# Sensor_Board.net
KiCad netlist of a schematic drawn in Altium Designer
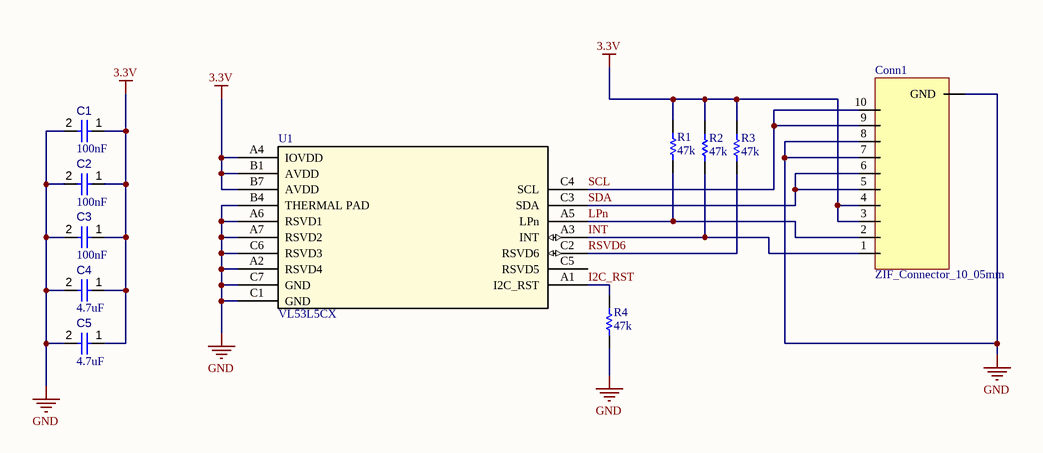
[diagram p0: Sensor_Board.SchDoc]

(export (version "E")
  (design (tool "Eeschema 10.0.6"))
  (components
    (comp (ref "C1")
      (value "100nF")
      (footprint "CAPC1608X90X40NL10T20")
      (description "Chip Capacitor, 100 nF, +/- 10%, 50 V, 0603 (1608 Metric)")
      (fields (field (name "TOLERANCE") "10%") (field (name "Comment") "Capacitor 100 nF +/-10% 50 V 0603"))
      (libsource (lib "Domen's Workpace") (part "CAP-NP-2"))
    )
    (comp (ref "C2")
      (value "100nF")
      (footprint "CAPC1608X90X40NL10T20")
      (description "Chip Capacitor, 100 nF, +/- 10%, 50 V, 0603 (1608 Metric)")
      (fields (field (name "TOLERANCE") "10%") (field (name "Comment") "Capacitor 100 nF +/-10% 50 V 0603"))
      (libsource (lib "Domen's Workpace") (part "CAP-NP-2"))
    )
    (comp (ref "C3")
      (value "100nF")
      (footprint "CAPC1608X90X40NL10T20")
      (description "Chip Capacitor, 100 nF, +/- 10%, 50 V, 0603 (1608 Metric)")
      (fields (field (name "TOLERANCE") "10%") (field (name "Comment") "Capacitor 100 nF +/-10% 50 V 0603"))
      (libsource (lib "Domen's Workpace") (part "CAP-NP-2"))
    )
    (comp (ref "C4")
      (value "4.7uF")
      (footprint "CAPC1608X90X40NL10T20")
      (description "Chip Capacitor, 100 nF, +/- 10%, 50 V, 0603 (1608 Metric)")
      (fields (field (name "TOLERANCE") "10%") (field (name "Comment") "Capacitor 100 nF +/-10% 50 V 0603"))
      (libsource (lib "Domen's Workpace") (part "CAP-NP-2"))
    )
    (comp (ref "C5")
      (value "4.7uF")
      (footprint "CAPC1608X90X40NL10T20")
      (description "Chip Capacitor, 100 nF, +/- 10%, 50 V, 0603 (1608 Metric)")
      (fields (field (name "TOLERANCE") "10%") (field (name "Comment") "Capacitor 100 nF +/-10% 50 V 0603"))
      (libsource (lib "Domen's Workpace") (part "CAP-NP-2"))
    )
    (comp (ref "Conn1")
      (value "ZIF_Connector_10_05mm")
      (footprint "ZIF_Connector_10_05mm")
      (libsource (lib "MainLib") (part "ZIF_Connector_10_05mm"))
    )
    (comp (ref "R1")
      (value "47k")
      (footprint "RESC1608X55X25NL10T15")
      (description "Chip Resistor, 0 Ohm, 0.1 W, -55 to 155 degC, 0603 (1608 Metric)")
      (fields (field (name "POWER") "100mW") (field (name "TOLERANCE") "5%"))
      (libsource (lib "Domen's Workpace") (part "RES-2"))
    )
    (comp (ref "R2")
      (value "47k")
      (footprint "RESC1608X55X25NL10T15")
      (description "Chip Resistor, 0 Ohm, 0.1 W, -55 to 155 degC, 0603 (1608 Metric)")
      (fields (field (name "POWER") "100mW") (field (name "TOLERANCE") "5%"))
      (libsource (lib "Domen's Workpace") (part "RES-2"))
    )
    (comp (ref "R3")
      (value "47k")
      (footprint "RESC1608X55X25NL10T15")
      (description "Chip Resistor, 0 Ohm, 0.1 W, -55 to 155 degC, 0603 (1608 Metric)")
      (fields (field (name "POWER") "100mW") (field (name "TOLERANCE") "5%"))
      (libsource (lib "Domen's Workpace") (part "RES-2"))
    )
    (comp (ref "R4")
      (value "47k")
      (footprint "RESC1608X55X25NL10T15")
      (description "Chip Resistor, 0 Ohm, 0.1 W, -55 to 155 degC, 0603 (1608 Metric)")
      (fields (field (name "POWER") "100mW") (field (name "TOLERANCE") "5%"))
      (libsource (lib "Domen's Workpace") (part "RES-2"))
    )
    (comp (ref "U1")
      (value "VL53L5CX")
      (footprint "vl53l5cx")
      (description "No Description Available")
      (fields
        (field (name "MANUFACTURER_PART_NUMBER") "VL53L5CXV0GC/1")
        (field (name "COPYRIGHT") "Copyright (C) 2022 Ultra Librarian. All rights reserved.")
      )
      (libsource (lib "MainLib") (part "VL53L5CX"))
    )
  )
  (nets
    (net (code "1") (name "/I2C_RST") (class "Default")
      (node (ref "R4") (pin "1") (pinfunction "1_1") (pintype "passive"))
      (node (ref "U1") (pin "A1") (pinfunction "I2C_RST_A1") (pintype "passive"))
    )
    (net (code "2") (name "/INT") (class "Default")
      (node (ref "Conn1") (pin "1") (pinfunction "1_1") (pintype "passive"))
      (node (ref "R2") (pin "2") (pinfunction "2_2") (pintype "passive"))
      (node (ref "U1") (pin "A3") (pinfunction "INT_A3") (pintype "bidirectional"))
    )
    (net (code "3") (name "/LPn") (class "Default")
      (node (ref "Conn1") (pin "2") (pinfunction "2_2") (pintype "passive"))
      (node (ref "R1") (pin "2") (pinfunction "2_2") (pintype "passive"))
      (node (ref "U1") (pin "A5") (pinfunction "LPn_A5") (pintype "passive"))
    )
    (net (code "4") (name "/RSVD6") (class "Default")
      (node (ref "R3") (pin "2") (pinfunction "2_2") (pintype "passive"))
      (node (ref "U1") (pin "C2") (pinfunction "RSVD6_C2") (pintype "bidirectional"))
    )
    (net (code "5") (name "/SCL") (class "Default")
      (node (ref "Conn1") (pin "10") (pinfunction "10_10") (pintype "passive"))
      (node (ref "Conn1") (pin "9") (pinfunction "9_9") (pintype "passive"))
      (node (ref "U1") (pin "C4") (pinfunction "SCL_C4") (pintype "passive"))
    )
    (net (code "6") (name "/SDA") (class "Default")
      (node (ref "Conn1") (pin "5") (pinfunction "5_5") (pintype "passive"))
      (node (ref "Conn1") (pin "6") (pinfunction "6_6") (pintype "passive"))
      (node (ref "U1") (pin "C3") (pinfunction "SDA_C3") (pintype "passive"))
    )
    (net (code "7") (name "3.3V") (class "Default")
      (node (ref "C1") (pin "1") (pinfunction "1_1") (pintype "passive"))
      (node (ref "C2") (pin "1") (pinfunction "1_1") (pintype "passive"))
      (node (ref "C3") (pin "1") (pinfunction "1_1") (pintype "passive"))
      (node (ref "C4") (pin "1") (pinfunction "1_1") (pintype "passive"))
      (node (ref "C5") (pin "1") (pinfunction "1_1") (pintype "passive"))
      (node (ref "Conn1") (pin "3") (pinfunction "3_3") (pintype "passive"))
      (node (ref "Conn1") (pin "4") (pinfunction "4_4") (pintype "passive"))
      (node (ref "R1") (pin "1") (pinfunction "1_1") (pintype "passive"))
      (node (ref "R2") (pin "1") (pinfunction "1_1") (pintype "passive"))
      (node (ref "R3") (pin "1") (pinfunction "1_1") (pintype "passive"))
      (node (ref "U1") (pin "A4") (pinfunction "IOVDD_A4") (pintype "power_in"))
      (node (ref "U1") (pin "B1") (pinfunction "AVDD_B1") (pintype "power_in"))
      (node (ref "U1") (pin "B7") (pinfunction "AVDD_B7") (pintype "power_in"))
    )
    (net (code "8") (name "GND") (class "Default")
      (node (ref "C1") (pin "2") (pinfunction "2_2") (pintype "passive"))
      (node (ref "C2") (pin "2") (pinfunction "2_2") (pintype "passive"))
      (node (ref "C3") (pin "2") (pinfunction "2_2") (pintype "passive"))
      (node (ref "C4") (pin "2") (pinfunction "2_2") (pintype "passive"))
      (node (ref "C5") (pin "2") (pinfunction "2_2") (pintype "passive"))
      (node (ref "Conn1") (pin "7") (pinfunction "7_7") (pintype "passive"))
      (node (ref "Conn1") (pin "8") (pinfunction "8_8") (pintype "passive"))
      (node (ref "Conn1") (pin "GND") (pinfunction "GND_GND") (pintype "passive"))
      (node (ref "R4") (pin "2") (pinfunction "2_2") (pintype "passive"))
      (node (ref "U1") (pin "A2") (pinfunction "RSVD4_A2") (pintype "passive"))
      (node (ref "U1") (pin "A6") (pinfunction "RSVD1_A6") (pintype "passive"))
      (node (ref "U1") (pin "A7") (pinfunction "RSVD2_A7") (pintype "passive"))
      (node (ref "U1") (pin "B4") (pinfunction "THERMAL_PAD_B4") (pintype "passive"))
      (node (ref "U1") (pin "C1") (pinfunction "GND_C1") (pintype "passive"))
      (node (ref "U1") (pin "C6") (pinfunction "RSVD3_C6") (pintype "passive"))
      (node (ref "U1") (pin "C7") (pinfunction "GND_C7") (pintype "passive"))
    )
    (net (code "9") (name "unconnected-(U1-RSVD5-PadC5)") (class "Default")
      (node (ref "U1") (pin "C5") (pinfunction "RSVD5_C5") (pintype "passive"))
    )
  )
)
